# Charging.net
KiCad netlist of a schematic drawn in Altium Designer
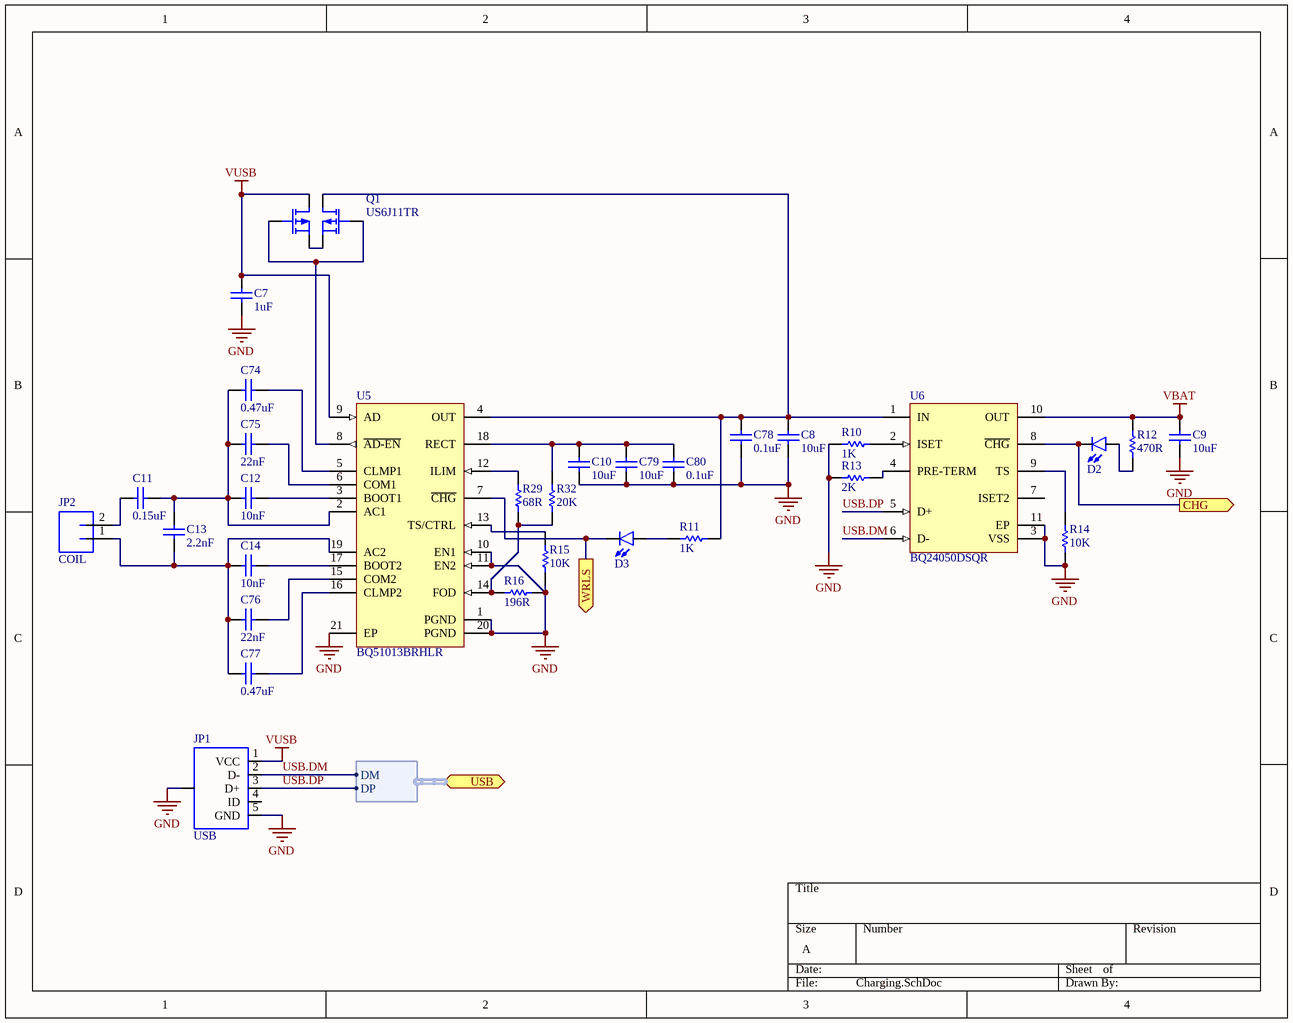
[diagram p0: Charging.SchDoc]

(export (version "E")
  (design (tool "Eeschema 10.0.6"))
  (components
    (comp (ref "C7")
      (value "1uF")
      (footprint "C0402[1005X55]")
      (description "1uF 6.3V 10% 0402 (1005 Metric)")
      (fields (field (name "PARTNUMBER") "GRM155R70J105KA12D") (field (name "MANUFACTURER") "Murata"))
      (libsource (lib "Capacitors") (part "CAP_1uF_6.3V_0402_10%"))
    )
    (comp (ref "C8")
      (value "10uF")
      (footprint "C0402[1005X55]")
      (description "10uF 6.3V 20% 0402 (1005 Metric)")
      (fields (field (name "PARTNUMBER") "GRM155R60J106ME44D") (field (name "MANUFACTURER") "Murata"))
      (libsource (lib "Capacitors") (part "CAP_10uF_6.3V_0402_20%"))
    )
    (comp (ref "C9")
      (value "10uF")
      (footprint "C0402[1005X55]")
      (description "10uF 6.3V 20% 0402 (1005 Metric)")
      (fields (field (name "PARTNUMBER") "GRM155R60J106ME44D") (field (name "MANUFACTURER") "Murata"))
      (libsource (lib "Capacitors") (part "CAP_10uF_6.3V_0402_20%"))
    )
    (comp (ref "C10")
      (value "10uF")
      (footprint "C0603[1608X92]")
      (description "10uF 16V 10% 0603 (1608 Metric)")
      (fields (field (name "PARTNUMBER") "GRM188R61C106KAALD") (field (name "MANUFACTURER") "Murata"))
      (libsource (lib "Capacitors") (part "CAP_10uF_16V_0603_10%"))
    )
    (comp (ref "C11")
      (value "0.15uF")
      (footprint "C0402[1005X55]")
      (description "0.15uF 25V 10% 0402 (1005 Metric)")
      (fields (field (name "PARTNUMBER") "C1005X6S1E154K050BC") (field (name "MANUFACTURER") "TDK"))
      (libsource (lib "Capacitors") (part "CAP_0.15uF_25V_0402_10%"))
    )
    (comp (ref "C12")
      (value "10nF")
      (footprint "C0402[1005X55]")
      (description "10nF 50V 10% 0402 (1005 Metric)")
      (fields (field (name "PARTNUMBER") "GCM155R71H103KA55D") (field (name "MANUFACTURER") "Murata"))
      (libsource (lib "Capacitors") (part "CAP_10nF_50V_0402_10%"))
    )
    (comp (ref "C13")
      (value "2.2nF")
      (footprint "C0402[1005X55]")
      (description "2.2nF 50V 10% 0402 (1005 Metric)")
      (fields (field (name "PARTNUMBER") "GCM155R71H222KA37D") (field (name "MANUFACTURER") "Murata"))
      (libsource (lib "Capacitors") (part "CAP_2.2nF_50V_0402_10%"))
    )
    (comp (ref "C14")
      (value "10nF")
      (footprint "C0402[1005X55]")
      (description "10nF 50V 10% 0402 (1005 Metric)")
      (fields (field (name "PARTNUMBER") "GCM155R71H103KA55D") (field (name "MANUFACTURER") "Murata"))
      (libsource (lib "Capacitors") (part "CAP_10nF_50V_0402_10%"))
    )
    (comp (ref "C74")
      (value "0.47uF")
      (footprint "C0402[1005X55]")
      (description "0.47uF 25V 10% 0402 (1005 Metric)")
      (fields (field (name "PARTNUMBER") "GRM155R61E474KE01D") (field (name "MANUFACTURER") "Murata"))
      (libsource (lib "Capacitors") (part "CAP_0.47uF_25V_0402_10%"))
    )
    (comp (ref "C75")
      (value "22nF")
      (footprint "C0402[1005X55]")
      (description "22nF 50V 10% 0402 (1005 Metric)")
      (fields (field (name "PARTNUMBER") "GRM155R71H223KA12J") (field (name "MANUFACTURER") "Murata"))
      (libsource (lib "Capacitors") (part "CAP_22nF_50V_0402_10%"))
    )
    (comp (ref "C76")
      (value "22nF")
      (footprint "C0402[1005X55]")
      (description "22nF 50V 10% 0402 (1005 Metric)")
      (fields (field (name "PARTNUMBER") "GRM155R71H223KA12J") (field (name "MANUFACTURER") "Murata"))
      (libsource (lib "Capacitors") (part "CAP_22nF_50V_0402_10%"))
    )
    (comp (ref "C77")
      (value "0.47uF")
      (footprint "C0402[1005X55]")
      (description "0.47uF 25V 10% 0402 (1005 Metric)")
      (fields (field (name "PARTNUMBER") "GRM155R61E474KE01D") (field (name "MANUFACTURER") "Murata"))
      (libsource (lib "Capacitors") (part "CAP_0.47uF_25V_0402_10%"))
    )
    (comp (ref "C78")
      (value "0.1uF")
      (footprint "C0402[1005X55]")
      (description "0.1uF 6.3V 10% 0402 (1005 Metric)")
      (fields (field (name "PARTNUMBER") "GRM155R70J104KA01D") (field (name "MANUFACTURER") "Murata"))
      (libsource (lib "Capacitors") (part "CAP_0.1uF_6.3V_0402_10%"))
    )
    (comp (ref "C79")
      (value "10uF")
      (footprint "C0603[1608X92]")
      (description "10uF 16V 10% 0603 (1608 Metric)")
      (fields (field (name "PARTNUMBER") "GRM188R61C106KAALD") (field (name "MANUFACTURER") "Murata"))
      (libsource (lib "Capacitors") (part "CAP_10uF_16V_0603_10%"))
    )
    (comp (ref "C80")
      (value "0.1uF")
      (footprint "C0402[1005X55]")
      (description "0.1uF 100V 10% 0402 (1005 Metric)")
      (fields (field (name "PARTNUMBER") "GRM155R62A104KE14D") (field (name "MANUFACTURER") "Murata"))
      (libsource (lib "Capacitors") (part "CAP_0.1uF_100V_0402_10%"))
    )
    (comp (ref "D2")
      (value "LED_0603_GREEN_5mA")
      (footprint "LED0603")
      (fields (field (name "PARTNUMBER") "LTST-C193TGKT-5A") (field (name "MANUFACTURER") "Lite-On Inc."))
      (libsource (lib "LEDs") (part "LED_0603_GREEN_5mA"))
    )
    (comp (ref "D3")
      (value "LED_0603_ORANGE_5mA")
      (footprint "LED0603")
      (fields (field (name "PARTNUMBER") "LTST-C193KFKT-5A") (field (name "MANUFACTURER") "Lite-On Inc."))
      (libsource (lib "LEDs") (part "LED_0603_ORANGE_5mA"))
    )
    (comp (ref "JP1")
      (value "USB")
      (footprint "USB-MICROB")
      (fields (field (name "PARTNUMBER") "10118192-0001LF") (field (name "MANUFACTURER") "Amphenol FCI"))
      (libsource (lib "Connectors") (part "USB_MICROB_SMT"))
    )
    (comp (ref "JP2")
      (value "COIL")
      (footprint "JST-SH-2-SMD-HORZ")
      (fields
        (field (name "MANUFACTURER") "JST Sales America, Inc.")
        (field (name "PARTNUMBER") "SM02B-SRSS-TB")
      )
      (libsource (lib "Connectors") (part "JST_SH_2_HORZ"))
    )
    (comp (ref "Q1")
      (value "US6J11TR")
      (footprint "SOT-363-6FL")
      (description "P-Channel MOSFET")
      (fields (field (name "MANUFACTURER") "ON Semiconductor"))
      (libsource (lib "MOSFETs") (part "US6J11TR"))
    )
    (comp (ref "R10")
      (value "1K")
      (footprint "R0402[1005]")
      (description "1K 0.063W 1% 0402 (1005 Metric)")
      (fields (field (name "MANUFACTURER") "KOA Speer") (field (name "PARTNUMBER") "RK73H1ETTP1001F"))
      (libsource (lib "Resistors") (part "RES_1K_0402_1%"))
    )
    (comp (ref "R11")
      (value "1K")
      (footprint "R0402[1005]")
      (description "1K 0.063W 1% 0402 (1005 Metric)")
      (fields (field (name "MANUFACTURER") "KOA Speer") (field (name "PARTNUMBER") "RK73H1ETTP1001F"))
      (libsource (lib "Resistors") (part "RES_1K_0402_1%"))
    )
    (comp (ref "R12")
      (value "470R")
      (footprint "R0402[1005]")
      (description "470R 0.063W 1% 0402 (1005 Metric)")
      (fields (field (name "MANUFACTURER") "KOA Speer") (field (name "PARTNUMBER") "RK73H1ETTP4700F"))
      (libsource (lib "Resistors") (part "RES_470R_0402_1%"))
    )
    (comp (ref "R13")
      (value "2K")
      (footprint "R0402[1005]")
      (description "2K 0.063W 1% 0402 (1005 Metric)")
      (fields (field (name "MANUFACTURER") "KOA Speer") (field (name "PARTNUMBER") "RK73H1ETTP2001F"))
      (libsource (lib "Resistors") (part "RES_2K_0402_1%"))
    )
    (comp (ref "R14")
      (value "10K")
      (footprint "R0402[1005]")
      (description "10K 0.063W 1% 0402 (1005 Metric)")
      (fields (field (name "MANUFACTURER") "KOA Speer") (field (name "PARTNUMBER") "RK73H1ETTP1002F"))
      (libsource (lib "Resistors") (part "RES_10K_0402_1%"))
    )
    (comp (ref "R15")
      (value "10K")
      (footprint "R0402[1005]")
      (description "10K 0.063W 1% 0402 (1005 Metric)")
      (fields (field (name "MANUFACTURER") "KOA Speer") (field (name "PARTNUMBER") "RK73H1ETTP1002F"))
      (libsource (lib "Resistors") (part "RES_10K_0402_1%"))
    )
    (comp (ref "R16")
      (value "196R")
      (footprint "R0402[1005]")
      (description "196R 0.063W 1% 0402 (1005 Metric)")
      (fields (field (name "MANUFACTURER") "KOA Speer") (field (name "PARTNUMBER") "RK73H1ETTP1960F"))
      (libsource (lib "Resistors") (part "RES_196R_0402_1%"))
    )
    (comp (ref "R29")
      (value "68R")
      (footprint "R0402[1005]")
      (description "68R 0.063W 1% 0402 (1005 Metric)")
      (fields (field (name "MANUFACTURER") "KOA Speer") (field (name "PARTNUMBER") "RK73H1ETTP68R0F"))
      (libsource (lib "Resistors") (part "RES_68R_0402_1%"))
    )
    (comp (ref "R32")
      (value "20K")
      (footprint "R0402[1005]")
      (description "20K 0.063W 1% 0402 (1005 Metric)")
      (fields (field (name "MANUFACTURER") "KOA Speer") (field (name "PARTNUMBER") "RK73H1ETTP2002F"))
      (libsource (lib "Resistors") (part "RES_20K_0402_1%"))
    )
    (comp (ref "U5")
      (value "BQ51013BRHLR")
      (footprint "VQFN-20")
      (fields (field (name "MANUFACTURER") "Texas Instruments"))
      (libsource (lib "ICs") (part "BQ51013BRHLR"))
    )
    (comp (ref "U6")
      (value "BQ24050DSQR")
      (footprint "WSON-10")
      (fields (field (name "MANUFACTURER") "Texas Instruments"))
      (libsource (lib "ICs") (part "BQ24050DSQR"))
    )
  )
  (nets
    (net (code "2") (name "/CHG") (class "Default")
      (node (ref "D2") (pin "C") (pinfunction "C_C") (pintype "passive"))
      (node (ref "U6") (pin "8") (pinfunction "~{CHG}_8") (pintype "tri_state"))
    )
    (net (code "3") (name "/USB.DM") (class "Default")
      (node (ref "JP1") (pin "2") (pinfunction "D-_2") (pintype "passive"))
      (node (ref "U6") (pin "6") (pinfunction "D-_6") (pintype "input"))
    )
    (net (code "4") (name "/USB.DP") (class "Default")
      (node (ref "JP1") (pin "3") (pinfunction "D+_3") (pintype "passive"))
      (node (ref "U6") (pin "5") (pinfunction "D+_5") (pintype "input"))
    )
    (net (code "5") (name "/WRLS") (class "Default")
      (node (ref "D3") (pin "C") (pinfunction "C_C") (pintype "passive"))
      (node (ref "U5") (pin "7") (pinfunction "~{CHG}_7") (pintype "open_collector"))
    )
    (net (code "7") (name "GND") (class "Default")
      (node (ref "C10") (pin "1") (pinfunction "1_1") (pintype "passive"))
      (node (ref "C7") (pin "1") (pinfunction "1_1") (pintype "passive"))
      (node (ref "C78") (pin "1") (pinfunction "1_1") (pintype "passive"))
      (node (ref "C79") (pin "1") (pinfunction "1_1") (pintype "passive"))
      (node (ref "C8") (pin "1") (pinfunction "1_1") (pintype "passive"))
      (node (ref "C80") (pin "1") (pinfunction "1_1") (pintype "passive"))
      (node (ref "C9") (pin "1") (pinfunction "1_1") (pintype "passive"))
      (node (ref "JP1") (pin "5") (pinfunction "GND_5") (pintype "passive"))
      (node (ref "JP1") (pin "6") (pinfunction "SHIELD_6") (pintype "passive"))
      (node (ref "R10") (pin "1") (pinfunction "1_1") (pintype "passive"))
      (node (ref "R13") (pin "1") (pinfunction "1_1") (pintype "passive"))
      (node (ref "R14") (pin "1") (pinfunction "1_1") (pintype "passive"))
      (node (ref "R15") (pin "1") (pinfunction "1_1") (pintype "passive"))
      (node (ref "R16") (pin "2") (pinfunction "2_2") (pintype "passive"))
      (node (ref "U5") (pin "1") (pinfunction "PGND_1") (pintype "power_in"))
      (node (ref "U5") (pin "10") (pinfunction "EN1_10") (pintype "input"))
      (node (ref "U5") (pin "11") (pinfunction "EN2_11") (pintype "input"))
      (node (ref "U5") (pin "20") (pinfunction "PGND_20") (pintype "power_in"))
      (node (ref "U5") (pin "21") (pinfunction "EP_21") (pintype "passive"))
      (node (ref "U6") (pin "11") (pinfunction "EP_11") (pintype "power_in"))
      (node (ref "U6") (pin "3") (pinfunction "VSS_3") (pintype "power_in"))
    )
    (net (code "8") (name "Net-(C11-Pad1)") (class "Default")
      (node (ref "C11") (pin "1") (pinfunction "1_1") (pintype "passive"))
      (node (ref "JP2") (pin "2") (pinfunction "2_2") (pintype "passive"))
    )
    (net (code "9") (name "Net-(D2-PadA)") (class "Default")
      (node (ref "D2") (pin "A") (pinfunction "A_A") (pintype "passive"))
      (node (ref "R12") (pin "1") (pinfunction "1_1") (pintype "passive"))
    )
    (net (code "10") (name "Net-(D3-PadA)") (class "Default")
      (node (ref "D3") (pin "A") (pinfunction "A_A") (pintype "passive"))
      (node (ref "R11") (pin "2") (pinfunction "2_2") (pintype "passive"))
    )
    (net (code "11") (name "Net-(Q1-D1)") (class "Default")
      (node (ref "C78") (pin "2") (pinfunction "2_2") (pintype "passive"))
      (node (ref "C8") (pin "2") (pinfunction "2_2") (pintype "passive"))
      (node (ref "Q1") (pin "6") (pinfunction "D1_6") (pintype "passive"))
      (node (ref "R11") (pin "1") (pinfunction "1_1") (pintype "passive"))
      (node (ref "U5") (pin "4") (pinfunction "OUT_4") (pintype "power_in"))
      (node (ref "U6") (pin "1") (pinfunction "IN_1") (pintype "power_in"))
    )
    (net (code "12") (name "Net-(Q1-G1)") (class "Default")
      (node (ref "Q1") (pin "2") (pinfunction "G1_2") (pintype "passive"))
      (node (ref "Q1") (pin "5") (pinfunction "G2_5") (pintype "passive"))
      (node (ref "U5") (pin "8") (pinfunction "~{AD-EN}_8") (pintype "output"))
    )
    (net (code "13") (name "Net-(Q1-S1)") (class "Default")
      (node (ref "Q1") (pin "1") (pinfunction "S1_1") (pintype "passive"))
      (node (ref "Q1") (pin "4") (pinfunction "S2_4") (pintype "passive"))
    )
    (net (code "14") (name "Net-(U5-AC1)") (class "Default")
      (node (ref "C11") (pin "2") (pinfunction "2_2") (pintype "passive"))
      (node (ref "C12") (pin "2") (pinfunction "2_2") (pintype "passive"))
      (node (ref "C13") (pin "2") (pinfunction "2_2") (pintype "passive"))
      (node (ref "C74") (pin "1") (pinfunction "1_1") (pintype "passive"))
      (node (ref "C75") (pin "1") (pinfunction "1_1") (pintype "passive"))
      (node (ref "U5") (pin "2") (pinfunction "AC1_2") (pintype "power_in"))
    )
    (net (code "15") (name "Net-(U5-AC2)") (class "Default")
      (node (ref "C13") (pin "1") (pinfunction "1_1") (pintype "passive"))
      (node (ref "C14") (pin "2") (pinfunction "2_2") (pintype "passive"))
      (node (ref "C76") (pin "1") (pinfunction "1_1") (pintype "passive"))
      (node (ref "C77") (pin "1") (pinfunction "1_1") (pintype "passive"))
      (node (ref "JP2") (pin "1") (pinfunction "1_1") (pintype "passive"))
      (node (ref "U5") (pin "19") (pinfunction "AC2_19") (pintype "power_in"))
    )
    (net (code "16") (name "Net-(U5-BOOT1)") (class "Default")
      (node (ref "C12") (pin "1") (pinfunction "1_1") (pintype "passive"))
      (node (ref "U5") (pin "3") (pinfunction "BOOT1_3") (pintype "passive"))
    )
    (net (code "17") (name "Net-(U5-BOOT2)") (class "Default")
      (node (ref "C14") (pin "1") (pinfunction "1_1") (pintype "passive"))
      (node (ref "U5") (pin "17") (pinfunction "BOOT2_17") (pintype "passive"))
    )
    (net (code "18") (name "Net-(U5-CLMP1)") (class "Default")
      (node (ref "C74") (pin "2") (pinfunction "2_2") (pintype "passive"))
      (node (ref "U5") (pin "5") (pinfunction "CLMP1_5") (pintype "open_collector"))
    )
    (net (code "19") (name "Net-(U5-CLMP2)") (class "Default")
      (node (ref "C77") (pin "2") (pinfunction "2_2") (pintype "passive"))
      (node (ref "U5") (pin "16") (pinfunction "CLMP2_16") (pintype "open_collector"))
    )
    (net (code "20") (name "Net-(U5-COM1)") (class "Default")
      (node (ref "C75") (pin "2") (pinfunction "2_2") (pintype "passive"))
      (node (ref "U5") (pin "6") (pinfunction "COM1_6") (pintype "open_collector"))
    )
    (net (code "21") (name "Net-(U5-COM2)") (class "Default")
      (node (ref "C76") (pin "2") (pinfunction "2_2") (pintype "passive"))
      (node (ref "U5") (pin "15") (pinfunction "COM2_15") (pintype "open_collector"))
    )
    (net (code "22") (name "Net-(U5-FOD)") (class "Default")
      (node (ref "R16") (pin "1") (pinfunction "1_1") (pintype "passive"))
      (node (ref "R29") (pin "1") (pinfunction "1_1") (pintype "passive"))
      (node (ref "R32") (pin "1") (pinfunction "1_1") (pintype "passive"))
      (node (ref "U5") (pin "14") (pinfunction "FOD_14") (pintype "input"))
    )
    (net (code "23") (name "Net-(U5-ILIM)") (class "Default")
      (node (ref "R29") (pin "2") (pinfunction "2_2") (pintype "passive"))
      (node (ref "U5") (pin "12") (pinfunction "ILIM_12") (pintype "input"))
    )
    (net (code "24") (name "Net-(U5-RECT)") (class "Default")
      (node (ref "C10") (pin "2") (pinfunction "2_2") (pintype "passive"))
      (node (ref "C79") (pin "2") (pinfunction "2_2") (pintype "passive"))
      (node (ref "C80") (pin "2") (pinfunction "2_2") (pintype "passive"))
      (node (ref "R32") (pin "2") (pinfunction "2_2") (pintype "passive"))
      (node (ref "U5") (pin "18") (pinfunction "RECT_18") (pintype "passive"))
    )
    (net (code "25") (name "Net-(U5-TS{slash}CTRL)") (class "Default")
      (node (ref "R15") (pin "2") (pinfunction "2_2") (pintype "passive"))
      (node (ref "U5") (pin "13") (pinfunction "TS/CTRL_13") (pintype "input"))
    )
    (net (code "26") (name "Net-(U6-ISET)") (class "Default")
      (node (ref "R10") (pin "2") (pinfunction "2_2") (pintype "passive"))
      (node (ref "U6") (pin "2") (pinfunction "ISET_2") (pintype "input"))
    )
    (net (code "27") (name "Net-(U6-PRE-TERM)") (class "Default")
      (node (ref "R13") (pin "2") (pinfunction "2_2") (pintype "passive"))
      (node (ref "U6") (pin "4") (pinfunction "PRE-TERM_4") (pintype "passive"))
    )
    (net (code "28") (name "Net-(U6-TS)") (class "Default")
      (node (ref "R14") (pin "2") (pinfunction "2_2") (pintype "passive"))
      (node (ref "U6") (pin "9") (pinfunction "TS_9") (pintype "passive"))
    )
    (net (code "29") (name "VBAT") (class "Default")
      (node (ref "C9") (pin "2") (pinfunction "2_2") (pintype "passive"))
      (node (ref "R12") (pin "2") (pinfunction "2_2") (pintype "passive"))
      (node (ref "U6") (pin "10") (pinfunction "OUT_10") (pintype "power_in"))
    )
    (net (code "30") (name "VUSB") (class "Default")
      (node (ref "C7") (pin "2") (pinfunction "2_2") (pintype "passive"))
      (node (ref "JP1") (pin "1") (pinfunction "VCC_1") (pintype "passive"))
      (node (ref "Q1") (pin "3") (pinfunction "D2_3") (pintype "passive"))
      (node (ref "U5") (pin "9") (pinfunction "AD_9") (pintype "input"))
    )
    (net (code "31") (name "unconnected-(JP1-ID-Pad4)") (class "Default")
      (node (ref "JP1") (pin "4") (pinfunction "ID_4") (pintype "passive"))
    )
    (net (code "32") (name "unconnected-(U6-ISET2-Pad7)") (class "Default")
      (node (ref "U6") (pin "7") (pinfunction "ISET2_7") (pintype "passive"))
    )
  )
)
